# Schematic.net
KiCad netlist of a schematic drawn in Altium Designer
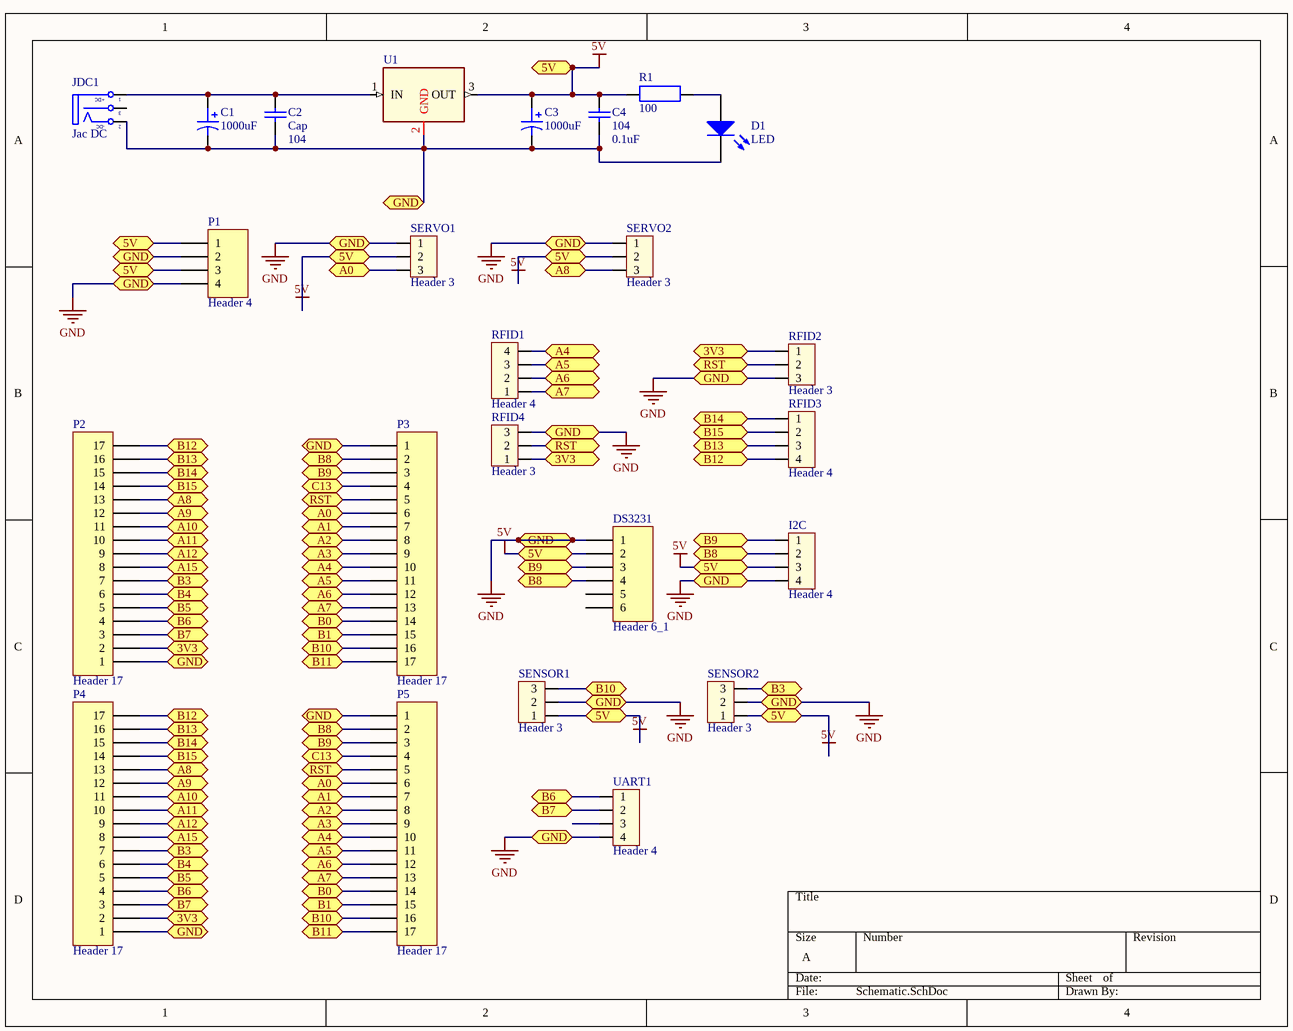
[diagram p0: Schematic.SchDoc]

(export (version "E")
  (design (tool "Eeschema 10.0.6"))
  (components
    (comp (ref "C1")
      (value "1000uF")
      (footprint "RADIAL C")
      (description "Polarized Capacitor")
      (fields (field (name "Comment") "Cap Pol") (field (name "PUBLISHER") "Altium Limited"))
      (libsource (lib "hphonglib") (part "Cap Pol"))
    )
    (comp (ref "C2")
      (value "Cap")
      (footprint "C3MM")
      (description "Capacitor")
      (fields (field (name "ALTIUM_VALUE") "104") (field (name "PUBLISHER") "Altium Limited"))
      (libsource (lib "hphonglib") (part "Cap"))
    )
    (comp (ref "C3")
      (value "1000uF")
      (footprint "RADIAL C")
      (description "Polarized Capacitor")
      (fields (field (name "Comment") "Cap Pol") (field (name "PUBLISHER") "Altium Limited"))
      (libsource (lib "hphonglib") (part "Cap Pol"))
    )
    (comp (ref "C4")
      (value "104")
      (footprint "C3MM")
      (description "Capacitor")
      (fields (field (name "ALTIUM_VALUE") "0.1uF") (field (name "PUBLISHER") "Altium Limited"))
      (libsource (lib "hphonglib") (part "Cap"))
    )
    (comp (ref "D1")
      (value "LED")
      (footprint "LED-0 5mm BLUE")
      (description "Typical LED")
      (fields (field (name "PUBLISHER") "Altium Limited"))
      (libsource (lib "hphonglib") (part "LED"))
    )
    (comp (ref "DS3231")
      (value "Header 6_1")
      (footprint "HDR1X6")
      (description "Header, 6-Pin")
      (fields (field (name "PUBLISHER") "Altium Limited"))
      (libsource (lib "hphonglib") (part "Header 6_1"))
    )
    (comp (ref "I2C")
      (value "Header 4")
      (footprint "HED4")
      (description "Header 4 (Green)")
      (libsource (lib "hphonglib") (part "Hed4"))
    )
    (comp (ref "JDC1")
      (value "Jac DC")
      (footprint "DC-IN")
      (description "Jac DC input")
      (libsource (lib "hphonglib") (part "DCIN"))
    )
    (comp (ref "P1")
      (value "Header 4")
      (footprint "Header 4")
      (description "Header, 4-Pin")
      (fields (field (name "PUBLISHER") "Altium Limited"))
      (libsource (lib "hphonglib") (part "Header 4"))
    )
    (comp (ref "P2")
      (value "Header 17")
      (footprint "HDR1X17")
      (description "Header, 17-Pin")
      (fields (field (name "PUBLISHER") "Altium Limited"))
      (libsource (lib "hphonglib") (part "Header 17"))
    )
    (comp (ref "P3")
      (value "Header 17")
      (footprint "HDR1X17")
      (description "Header, 17-Pin")
      (fields (field (name "PUBLISHER") "Altium Limited"))
      (libsource (lib "") (part "Header 17_1"))
    )
    (comp (ref "P4")
      (value "Header 17")
      (footprint "HDR1X17")
      (description "Header, 17-Pin")
      (fields (field (name "PUBLISHER") "Altium Limited"))
      (libsource (lib "hphonglib") (part "Header 17"))
    )
    (comp (ref "P5")
      (value "Header 17")
      (footprint "HDR1X17")
      (description "Header, 17-Pin")
      (fields (field (name "PUBLISHER") "Altium Limited"))
      (libsource (lib "") (part "Header 17_1"))
    )
    (comp (ref "R1")
      (value "100")
      (footprint "R1W")
      (description "Resistor 1W")
      (libsource (lib "hphonglib") (part "R1W"))
    )
    (comp (ref "RFID1")
      (value "Header 4")
      (footprint "HED4")
      (description "Header 4 (Green)")
      (libsource (lib "") (part "Hed4_1"))
    )
    (comp (ref "RFID2")
      (value "Header 3")
      (footprint "HED3")
      (description "Header 3 (Green)")
      (libsource (lib "") (part "Hed3_1"))
    )
    (comp (ref "RFID3")
      (value "Header 4")
      (footprint "HED4")
      (description "Header 4 (Green)")
      (libsource (lib "hphonglib") (part "Hed4"))
    )
    (comp (ref "RFID4")
      (value "Header 3")
      (footprint "HED3")
      (description "Header 3 (Green)")
      (libsource (lib "hphonglib") (part "Hed3"))
    )
    (comp (ref "SENSOR1")
      (value "Header 3")
      (footprint "HED3")
      (description "Header 3 (Green)")
      (libsource (lib "hphonglib") (part "Hed3"))
    )
    (comp (ref "SENSOR2")
      (value "Header 3")
      (footprint "HED3")
      (description "Header 3 (Green)")
      (libsource (lib "hphonglib") (part "Hed3"))
    )
    (comp (ref "SERVO1")
      (value "Header 3")
      (footprint "HED3")
      (description "Header 3 (Green)")
      (libsource (lib "") (part "Hed3_1"))
    )
    (comp (ref "SERVO2")
      (value "Header 3")
      (footprint "HED3")
      (description "Header 3 (Green)")
      (libsource (lib "") (part "Hed3_1"))
    )
    (comp (ref "U1")
      (value "LM78xx")
      (footprint "TO-220")
      (description "Regulator")
      (fields
        (field (name "MANUFACTURER") "Fairchild Semiconductor Corporation")
        (field (name "TOLERANCE") "4 %")
        (field (name "PUBLISHER") "Hoang Nguyen")
      )
      (libsource (lib "hphonglib") (part "LM78xx"))
    )
    (comp (ref "UART1")
      (value "Header 4")
      (footprint "HED4")
      (description "Header 4 (Green)")
      (libsource (lib "hphonglib") (part "Hed4"))
    )
  )
  (nets
    (net (code "1") (name "/3V3") (class "Default")
      (node (ref "P2") (pin "2") (pinfunction "2_2") (pintype "passive"))
      (node (ref "P4") (pin "2") (pinfunction "2_2") (pintype "passive"))
      (node (ref "RFID2") (pin "1") (pinfunction "1_1") (pintype "passive"))
      (node (ref "RFID4") (pin "1") (pinfunction "1_1") (pintype "passive"))
    )
    (net (code "2") (name "/A0") (class "Default")
      (node (ref "P3") (pin "6") (pinfunction "6_6") (pintype "passive"))
      (node (ref "P5") (pin "6") (pinfunction "6_6") (pintype "passive"))
      (node (ref "SERVO1") (pin "3") (pinfunction "3_3") (pintype "passive"))
    )
    (net (code "3") (name "/A1") (class "Default")
      (node (ref "P3") (pin "7") (pinfunction "7_7") (pintype "passive"))
      (node (ref "P5") (pin "7") (pinfunction "7_7") (pintype "passive"))
    )
    (net (code "4") (name "/A2") (class "Default")
      (node (ref "P3") (pin "8") (pinfunction "8_8") (pintype "passive"))
      (node (ref "P5") (pin "8") (pinfunction "8_8") (pintype "passive"))
    )
    (net (code "5") (name "/A3") (class "Default")
      (node (ref "P3") (pin "9") (pinfunction "9_9") (pintype "passive"))
      (node (ref "P5") (pin "9") (pinfunction "9_9") (pintype "passive"))
    )
    (net (code "6") (name "/A4") (class "Default")
      (node (ref "P3") (pin "10") (pinfunction "10_10") (pintype "passive"))
      (node (ref "P5") (pin "10") (pinfunction "10_10") (pintype "passive"))
      (node (ref "RFID1") (pin "4") (pinfunction "4_4") (pintype "passive"))
    )
    (net (code "7") (name "/A5") (class "Default")
      (node (ref "P3") (pin "11") (pinfunction "11_11") (pintype "passive"))
      (node (ref "P5") (pin "11") (pinfunction "11_11") (pintype "passive"))
      (node (ref "RFID1") (pin "3") (pinfunction "3_3") (pintype "passive"))
    )
    (net (code "8") (name "/A6") (class "Default")
      (node (ref "P3") (pin "12") (pinfunction "12_12") (pintype "passive"))
      (node (ref "P5") (pin "12") (pinfunction "12_12") (pintype "passive"))
      (node (ref "RFID1") (pin "2") (pinfunction "2_2") (pintype "passive"))
    )
    (net (code "9") (name "/A7") (class "Default")
      (node (ref "P3") (pin "13") (pinfunction "13_13") (pintype "passive"))
      (node (ref "P5") (pin "13") (pinfunction "13_13") (pintype "passive"))
      (node (ref "RFID1") (pin "1") (pinfunction "1_1") (pintype "passive"))
    )
    (net (code "10") (name "/A8") (class "Default")
      (node (ref "P2") (pin "13") (pinfunction "13_13") (pintype "passive"))
      (node (ref "P4") (pin "13") (pinfunction "13_13") (pintype "passive"))
      (node (ref "SERVO2") (pin "3") (pinfunction "3_3") (pintype "passive"))
    )
    (net (code "11") (name "/A9") (class "Default")
      (node (ref "P2") (pin "12") (pinfunction "12_12") (pintype "passive"))
      (node (ref "P4") (pin "12") (pinfunction "12_12") (pintype "passive"))
    )
    (net (code "12") (name "/A10") (class "Default")
      (node (ref "P2") (pin "11") (pinfunction "11_11") (pintype "passive"))
      (node (ref "P4") (pin "11") (pinfunction "11_11") (pintype "passive"))
    )
    (net (code "13") (name "/A11") (class "Default")
      (node (ref "P2") (pin "10") (pinfunction "10_10") (pintype "passive"))
      (node (ref "P4") (pin "10") (pinfunction "10_10") (pintype "passive"))
    )
    (net (code "14") (name "/A12") (class "Default")
      (node (ref "P2") (pin "9") (pinfunction "9_9") (pintype "passive"))
      (node (ref "P4") (pin "9") (pinfunction "9_9") (pintype "passive"))
    )
    (net (code "15") (name "/A15") (class "Default")
      (node (ref "P2") (pin "8") (pinfunction "8_8") (pintype "passive"))
      (node (ref "P4") (pin "8") (pinfunction "8_8") (pintype "passive"))
    )
    (net (code "16") (name "/B0") (class "Default")
      (node (ref "P3") (pin "14") (pinfunction "14_14") (pintype "passive"))
      (node (ref "P5") (pin "14") (pinfunction "14_14") (pintype "passive"))
    )
    (net (code "17") (name "/B1") (class "Default")
      (node (ref "P3") (pin "15") (pinfunction "15_15") (pintype "passive"))
      (node (ref "P5") (pin "15") (pinfunction "15_15") (pintype "passive"))
    )
    (net (code "18") (name "/B3") (class "Default")
      (node (ref "P2") (pin "7") (pinfunction "7_7") (pintype "passive"))
      (node (ref "P4") (pin "7") (pinfunction "7_7") (pintype "passive"))
      (node (ref "SENSOR2") (pin "3") (pinfunction "3_3") (pintype "passive"))
    )
    (net (code "19") (name "/B4") (class "Default")
      (node (ref "P2") (pin "6") (pinfunction "6_6") (pintype "passive"))
      (node (ref "P4") (pin "6") (pinfunction "6_6") (pintype "passive"))
    )
    (net (code "20") (name "/B5") (class "Default")
      (node (ref "P2") (pin "5") (pinfunction "5_5") (pintype "passive"))
      (node (ref "P4") (pin "5") (pinfunction "5_5") (pintype "passive"))
    )
    (net (code "21") (name "/B6") (class "Default")
      (node (ref "P2") (pin "4") (pinfunction "4_4") (pintype "passive"))
      (node (ref "P4") (pin "4") (pinfunction "4_4") (pintype "passive"))
      (node (ref "UART1") (pin "1") (pinfunction "1_1") (pintype "passive"))
    )
    (net (code "22") (name "/B7") (class "Default")
      (node (ref "P2") (pin "3") (pinfunction "3_3") (pintype "passive"))
      (node (ref "P4") (pin "3") (pinfunction "3_3") (pintype "passive"))
      (node (ref "UART1") (pin "2") (pinfunction "2_2") (pintype "passive"))
    )
    (net (code "23") (name "/B8") (class "Default")
      (node (ref "DS3231") (pin "4") (pinfunction "4_4") (pintype "passive"))
      (node (ref "I2C") (pin "2") (pinfunction "2_2") (pintype "passive"))
      (node (ref "P3") (pin "2") (pinfunction "2_2") (pintype "passive"))
      (node (ref "P5") (pin "2") (pinfunction "2_2") (pintype "passive"))
    )
    (net (code "24") (name "/B9") (class "Default")
      (node (ref "DS3231") (pin "3") (pinfunction "3_3") (pintype "passive"))
      (node (ref "I2C") (pin "1") (pinfunction "1_1") (pintype "passive"))
      (node (ref "P3") (pin "3") (pinfunction "3_3") (pintype "passive"))
      (node (ref "P5") (pin "3") (pinfunction "3_3") (pintype "passive"))
    )
    (net (code "25") (name "/B10") (class "Default")
      (node (ref "P3") (pin "16") (pinfunction "16_16") (pintype "passive"))
      (node (ref "P5") (pin "16") (pinfunction "16_16") (pintype "passive"))
      (node (ref "SENSOR1") (pin "3") (pinfunction "3_3") (pintype "passive"))
    )
    (net (code "26") (name "/B11") (class "Default")
      (node (ref "P3") (pin "17") (pinfunction "17_17") (pintype "passive"))
      (node (ref "P5") (pin "17") (pinfunction "17_17") (pintype "passive"))
    )
    (net (code "27") (name "/B12") (class "Default")
      (node (ref "P2") (pin "17") (pinfunction "17_17") (pintype "passive"))
      (node (ref "P4") (pin "17") (pinfunction "17_17") (pintype "passive"))
      (node (ref "RFID3") (pin "4") (pinfunction "4_4") (pintype "passive"))
    )
    (net (code "28") (name "/B13") (class "Default")
      (node (ref "P2") (pin "16") (pinfunction "16_16") (pintype "passive"))
      (node (ref "P4") (pin "16") (pinfunction "16_16") (pintype "passive"))
      (node (ref "RFID3") (pin "3") (pinfunction "3_3") (pintype "passive"))
    )
    (net (code "29") (name "/B14") (class "Default")
      (node (ref "P2") (pin "15") (pinfunction "15_15") (pintype "passive"))
      (node (ref "P4") (pin "15") (pinfunction "15_15") (pintype "passive"))
      (node (ref "RFID3") (pin "1") (pinfunction "1_1") (pintype "passive"))
    )
    (net (code "30") (name "/B15") (class "Default")
      (node (ref "P2") (pin "14") (pinfunction "14_14") (pintype "passive"))
      (node (ref "P4") (pin "14") (pinfunction "14_14") (pintype "passive"))
      (node (ref "RFID3") (pin "2") (pinfunction "2_2") (pintype "passive"))
    )
    (net (code "31") (name "/C13") (class "Default")
      (node (ref "P3") (pin "4") (pinfunction "4_4") (pintype "passive"))
      (node (ref "P5") (pin "4") (pinfunction "4_4") (pintype "passive"))
    )
    (net (code "32") (name "/RST") (class "Default")
      (node (ref "P3") (pin "5") (pinfunction "5_5") (pintype "passive"))
      (node (ref "P5") (pin "5") (pinfunction "5_5") (pintype "passive"))
      (node (ref "RFID2") (pin "2") (pinfunction "2_2") (pintype "passive"))
      (node (ref "RFID4") (pin "2") (pinfunction "2_2") (pintype "passive"))
    )
    (net (code "33") (name "5V") (class "Default")
      (node (ref "C3") (pin "1") (pinfunction "1_1") (pintype "passive"))
      (node (ref "C4") (pin "2") (pinfunction "2_2") (pintype "passive"))
      (node (ref "DS3231") (pin "2") (pinfunction "2_2") (pintype "passive"))
      (node (ref "I2C") (pin "3") (pinfunction "3_3") (pintype "passive"))
      (node (ref "P1") (pin "1") (pinfunction "1_1") (pintype "passive"))
      (node (ref "P1") (pin "3") (pinfunction "3_3") (pintype "passive"))
      (node (ref "R1") (pin "1") (pinfunction "1_1") (pintype "passive"))
      (node (ref "SENSOR1") (pin "1") (pinfunction "1_1") (pintype "passive"))
      (node (ref "SENSOR2") (pin "1") (pinfunction "1_1") (pintype "passive"))
      (node (ref "SERVO1") (pin "2") (pinfunction "2_2") (pintype "passive"))
      (node (ref "SERVO2") (pin "2") (pinfunction "2_2") (pintype "passive"))
      (node (ref "U1") (pin "3") (pinfunction "OUT_3") (pintype "output"))
    )
    (net (code "34") (name "GND") (class "Default")
      (node (ref "C1") (pin "2") (pinfunction "2_2") (pintype "passive"))
      (node (ref "C2") (pin "1") (pinfunction "1_1") (pintype "passive"))
      (node (ref "C3") (pin "2") (pinfunction "2_2") (pintype "passive"))
      (node (ref "C4") (pin "1") (pinfunction "1_1") (pintype "passive"))
      (node (ref "D1") (pin "2") (pinfunction "K_2") (pintype "passive"))
      (node (ref "DS3231") (pin "1") (pinfunction "1_1") (pintype "passive"))
      (node (ref "I2C") (pin "4") (pinfunction "4_4") (pintype "passive"))
      (node (ref "JDC1") (pin "2") (pinfunction "TN_2") (pintype "passive"))
      (node (ref "P1") (pin "2") (pinfunction "2_2") (pintype "passive"))
      (node (ref "P1") (pin "4") (pinfunction "4_4") (pintype "passive"))
      (node (ref "P2") (pin "1") (pinfunction "1_1") (pintype "passive"))
      (node (ref "P3") (pin "1") (pinfunction "1_1") (pintype "passive"))
      (node (ref "P4") (pin "1") (pinfunction "1_1") (pintype "passive"))
      (node (ref "P5") (pin "1") (pinfunction "1_1") (pintype "passive"))
      (node (ref "RFID2") (pin "3") (pinfunction "3_3") (pintype "passive"))
      (node (ref "RFID4") (pin "3") (pinfunction "3_3") (pintype "passive"))
      (node (ref "SENSOR1") (pin "2") (pinfunction "2_2") (pintype "passive"))
      (node (ref "SENSOR2") (pin "2") (pinfunction "2_2") (pintype "passive"))
      (node (ref "SERVO1") (pin "1") (pinfunction "1_1") (pintype "passive"))
      (node (ref "SERVO2") (pin "1") (pinfunction "1_1") (pintype "passive"))
      (node (ref "U1") (pin "2") (pinfunction "GND_2") (pintype "power_in"))
      (node (ref "UART1") (pin "4") (pinfunction "4_4") (pintype "passive"))
    )
    (net (code "35") (name "Net-(D1-A)") (class "Default")
      (node (ref "D1") (pin "1") (pinfunction "A_1") (pintype "passive"))
      (node (ref "R1") (pin "2") (pinfunction "2_2") (pintype "passive"))
    )
    (net (code "36") (name "Net-(JDC1-T)") (class "Default")
      (node (ref "C1") (pin "1") (pinfunction "1_1") (pintype "passive"))
      (node (ref "C2") (pin "2") (pinfunction "2_2") (pintype "passive"))
      (node (ref "JDC1") (pin "1") (pinfunction "T_1") (pintype "passive"))
      (node (ref "U1") (pin "1") (pinfunction "IN_1") (pintype "input"))
    )
    (net (code "37") (name "unconnected-(DS3231-Pad5)") (class "Default")
      (node (ref "DS3231") (pin "5") (pinfunction "5_5") (pintype "passive"))
    )
    (net (code "38") (name "unconnected-(DS3231-Pad6)") (class "Default")
      (node (ref "DS3231") (pin "6") (pinfunction "6_6") (pintype "passive"))
    )
    (net (code "39") (name "unconnected-(JDC1-S-Pad3)") (class "Default")
      (node (ref "JDC1") (pin "3") (pinfunction "S_3") (pintype "power_in"))
    )
    (net (code "40") (name "unconnected-(UART1-Pad3)") (class "Default")
      (node (ref "UART1") (pin "3") (pinfunction "3_3") (pintype "passive"))
    )
  )
)
